# timer.net
KiCad netlist of a schematic drawn in EAGLE
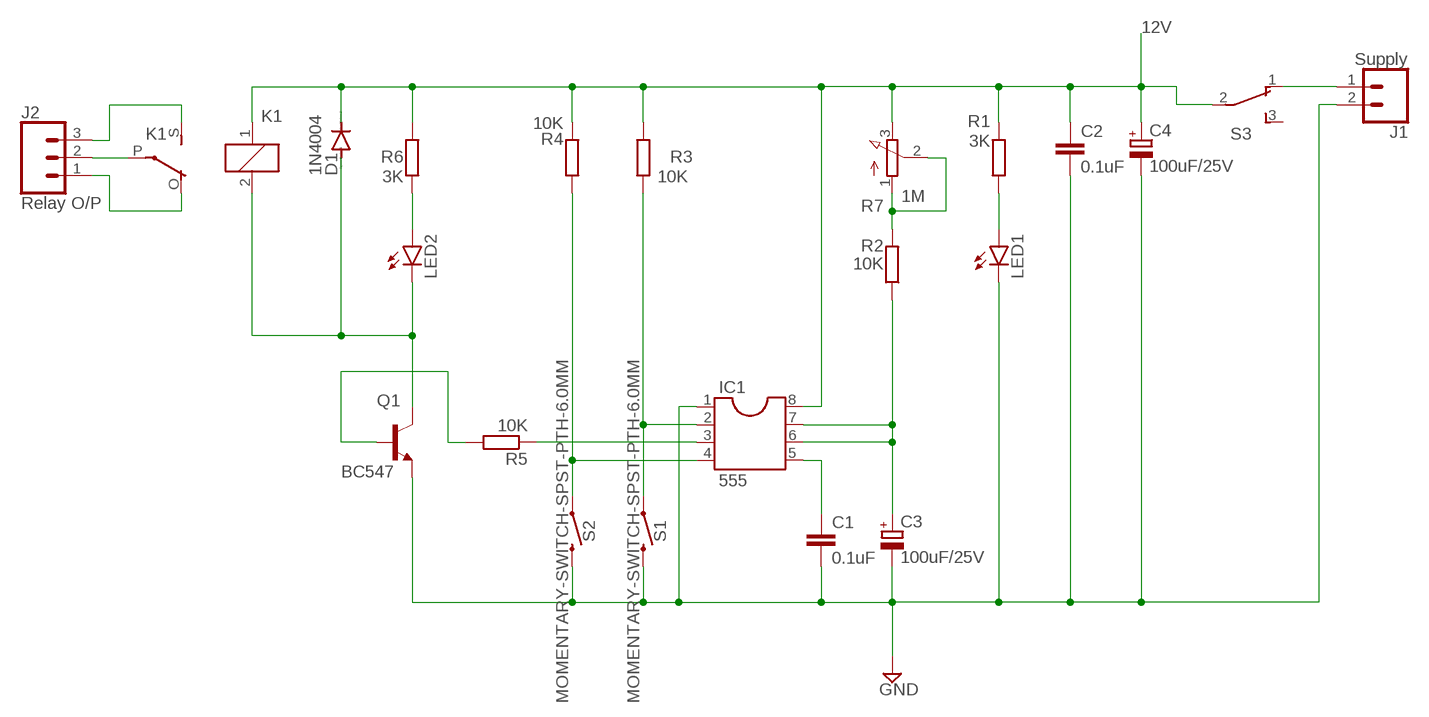
[diagram p0: schematic, sheet 1]

(export (version "E")
  (design (tool "Eeschema 10.0.6"))
  (components
    (comp (ref "C1")
      (value "0.1uF")
      (footprint "eagle-import:C025-050X050")
      (libsource (lib "eagle-import") (part "C-EU025-050X050"))
    )
    (comp (ref "C2")
      (value "0.1uF")
      (footprint "eagle-import:C025-050X050")
      (libsource (lib "eagle-import") (part "C-EU025-050X050"))
    )
    (comp (ref "C3")
      (value "100uF/25V")
      (footprint "eagle-import:E2,5-6")
      (libsource (lib "eagle-import") (part "CPOL-EUE2.5-6"))
    )
    (comp (ref "C4")
      (value "100uF/25V")
      (footprint "eagle-import:E2,5-6")
      (libsource (lib "eagle-import") (part "CPOL-EUE2.5-6"))
    )
    (comp (ref "D1")
      (value "1N4004")
      (footprint "eagle-import:DO41-10")
      (libsource (lib "eagle-import") (part "1N4004"))
    )
    (comp (ref "IC1")
      (value "555")
      (footprint "eagle-import:SOCKET-08")
      (libsource (lib "eagle-import") (part "DIL8S"))
    )
    (comp (ref "J1")
      (value "Supply")
      (footprint "eagle-import:SCREWTERMINAL-5MM-2")
      (libsource (lib "eagle-import") (part "CONN_025MM"))
    )
    (comp (ref "J2")
      (value "Relay O/P")
      (footprint "eagle-import:SCREWTERMINAL-5MM-3")
      (libsource (lib "eagle-import") (part "CONN_03-SCREW-5MM"))
    )
    (comp (ref "K1")
      (value "ZF112")
      (footprint "eagle-import:ZF112")
      (libsource (lib "eagle-import") (part "ZF112"))
    )
    (comp (ref "LED1")
      (value "LED5MM")
      (footprint "eagle-import:LED5MM")
      (libsource (lib "eagle-import") (part "LED5MM"))
    )
    (comp (ref "LED2")
      (value "LED5MM")
      (footprint "eagle-import:LED5MM")
      (libsource (lib "eagle-import") (part "LED5MM"))
    )
    (comp (ref "Q1")
      (value "BC547")
      (footprint "eagle-import:TO92")
      (libsource (lib "eagle-import") (part "BC547"))
    )
    (comp (ref "R1")
      (value "3K")
      (footprint "eagle-import:0207_10")
      (libsource (lib "eagle-import") (part "R-EU_0207/10"))
    )
    (comp (ref "R2")
      (value "10K")
      (footprint "eagle-import:0207_10")
      (libsource (lib "eagle-import") (part "R-EU_0207/10"))
    )
    (comp (ref "R3")
      (value "10K")
      (footprint "eagle-import:0207_10")
      (libsource (lib "eagle-import") (part "R-EU_0207/10"))
    )
    (comp (ref "R4")
      (value "10K")
      (footprint "eagle-import:0207_10")
      (libsource (lib "eagle-import") (part "R-EU_0207/10"))
    )
    (comp (ref "R5")
      (value "10K")
      (footprint "eagle-import:0207_10")
      (libsource (lib "eagle-import") (part "R-EU_0207/10"))
    )
    (comp (ref "R6")
      (value "3K")
      (footprint "eagle-import:0207_10")
      (libsource (lib "eagle-import") (part "R-EU_0207/10"))
    )
    (comp (ref "R7")
      (value "1M")
      (footprint "eagle-import:3RP_1610N")
      (libsource (lib "eagle-import") (part "3RP/1610N"))
    )
    (comp (ref "S1")
      (value "MOMENTARY-SWITCH-SPST-PTH-6.0MM")
      (footprint "eagle-import:TACTILE_SWITCH_PTH_6.0MM")
      (libsource (lib "eagle-import") (part "MOMENTARY-SWITCH-SPST-PTH-6.0MM"))
    )
    (comp (ref "S2")
      (value "MOMENTARY-SWITCH-SPST-PTH-6.0MM")
      (footprint "eagle-import:TACTILE_SWITCH_PTH_6.0MM")
      (libsource (lib "eagle-import") (part "MOMENTARY-SWITCH-SPST-PTH-6.0MM"))
    )
    (comp (ref "S3")
      (value "TL36YO")
      (footprint "eagle-import:TL3XYO")
      (libsource (lib "eagle-import") (part "TL36YO"))
    )
  )
  (nets
    (net (code "1") (name "/12V") (class "Default")
      (node (ref "C2") (pin "1") (pinfunction "1_1") (pintype "passive"))
      (node (ref "C4") (pin "+") (pinfunction "+_+") (pintype "passive"))
      (node (ref "D1") (pin "C") (pinfunction "C_C") (pintype "passive"))
      (node (ref "IC1") (pin "8") (pinfunction "8_8") (pintype "passive"))
      (node (ref "K1") (pin "1") (pinfunction "1_1") (pintype "passive"))
      (node (ref "R1") (pin "2") (pinfunction "2_2") (pintype "passive"))
      (node (ref "R3") (pin "2") (pinfunction "2_2") (pintype "passive"))
      (node (ref "R4") (pin "2") (pinfunction "2_2") (pintype "passive"))
      (node (ref "R6") (pin "2") (pinfunction "2_2") (pintype "passive"))
      (node (ref "R7") (pin "3") (pinfunction "E_3") (pintype "passive"))
      (node (ref "S3") (pin "2") (pinfunction "P_2") (pintype "passive"))
    )
    (net (code "2") (name "GND") (class "Default")
      (node (ref "C1") (pin "2") (pinfunction "2_2") (pintype "passive"))
      (node (ref "C2") (pin "2") (pinfunction "2_2") (pintype "passive"))
      (node (ref "C3") (pin "-") (pinfunction "-_-") (pintype "passive"))
      (node (ref "C4") (pin "-") (pinfunction "-_-") (pintype "passive"))
      (node (ref "IC1") (pin "1") (pinfunction "1_1") (pintype "passive"))
      (node (ref "J1") (pin "2") (pinfunction "2_2") (pintype "passive"))
      (node (ref "LED1") (pin "K") (pinfunction "C_K") (pintype "passive"))
      (node (ref "Q1") (pin "1") (pinfunction "E_1") (pintype "passive"))
      (node (ref "S1") (pin "3") (pinfunction "2_3") (pintype "passive"))
      (node (ref "S2") (pin "3") (pinfunction "2_3") (pintype "passive"))
    )
    (net (code "3") (name "Net-(C1-Pad1)") (class "Default")
      (node (ref "C1") (pin "1") (pinfunction "1_1") (pintype "passive"))
      (node (ref "IC1") (pin "5") (pinfunction "5_5") (pintype "passive"))
    )
    (net (code "4") (name "Net-(C3-Pad+)") (class "Default")
      (node (ref "C3") (pin "+") (pinfunction "+_+") (pintype "passive"))
      (node (ref "IC1") (pin "6") (pinfunction "6_6") (pintype "passive"))
      (node (ref "IC1") (pin "7") (pinfunction "7_7") (pintype "passive"))
      (node (ref "R2") (pin "1") (pinfunction "1_1") (pintype "passive"))
    )
    (net (code "5") (name "Net-(IC1-Pad2)") (class "Default")
      (node (ref "IC1") (pin "2") (pinfunction "2_2") (pintype "passive"))
      (node (ref "R3") (pin "1") (pinfunction "1_1") (pintype "passive"))
      (node (ref "S1") (pin "1") (pinfunction "1_1") (pintype "passive"))
    )
    (net (code "6") (name "Net-(IC1-Pad3)") (class "Default")
      (node (ref "IC1") (pin "3") (pinfunction "3_3") (pintype "passive"))
      (node (ref "R5") (pin "1") (pinfunction "1_1") (pintype "passive"))
    )
    (net (code "7") (name "Net-(IC1-Pad4)") (class "Default")
      (node (ref "IC1") (pin "4") (pinfunction "4_4") (pintype "passive"))
      (node (ref "R4") (pin "1") (pinfunction "1_1") (pintype "passive"))
      (node (ref "S2") (pin "1") (pinfunction "1_1") (pintype "passive"))
    )
    (net (code "8") (name "Net-(J2-Pad1)") (class "Default")
      (node (ref "J2") (pin "1") (pinfunction "1_1") (pintype "passive"))
      (node (ref "K1") (pin "O") (pinfunction "O_O") (pintype "passive"))
    )
    (net (code "9") (name "Net-(J2-Pad2)") (class "Default")
      (node (ref "J2") (pin "2") (pinfunction "2_2") (pintype "passive"))
      (node (ref "K1") (pin "P") (pinfunction "P_P") (pintype "passive"))
    )
    (net (code "10") (name "Net-(J2-Pad3)") (class "Default")
      (node (ref "J2") (pin "3") (pinfunction "3_3") (pintype "passive"))
      (node (ref "K1") (pin "S") (pinfunction "S_S") (pintype "passive"))
    )
    (net (code "11") (name "Net-(LED1-PadA)") (class "Default")
      (node (ref "LED1") (pin "A") (pinfunction "A_A") (pintype "passive"))
      (node (ref "R1") (pin "1") (pinfunction "1_1") (pintype "passive"))
    )
    (net (code "12") (name "Net-(LED2-C)") (class "Default")
      (node (ref "D1") (pin "A") (pinfunction "A_A") (pintype "passive"))
      (node (ref "K1") (pin "2") (pinfunction "2_2") (pintype "passive"))
      (node (ref "LED2") (pin "K") (pinfunction "C_K") (pintype "passive"))
      (node (ref "Q1") (pin "3") (pinfunction "C_3") (pintype "passive"))
    )
    (net (code "13") (name "Net-(LED2-PadA)") (class "Default")
      (node (ref "LED2") (pin "A") (pinfunction "A_A") (pintype "passive"))
      (node (ref "R6") (pin "1") (pinfunction "1_1") (pintype "passive"))
    )
    (net (code "14") (name "Net-(Q1-B)") (class "Default")
      (node (ref "Q1") (pin "2") (pinfunction "B_2") (pintype "passive"))
      (node (ref "R5") (pin "2") (pinfunction "2_2") (pintype "passive"))
    )
    (net (code "15") (name "Net-(R7-A)") (class "Default")
      (node (ref "R2") (pin "2") (pinfunction "2_2") (pintype "passive"))
      (node (ref "R7") (pin "1") (pinfunction "A_1") (pintype "passive"))
      (node (ref "R7") (pin "2") (pinfunction "S_2") (pintype "passive"))
    )
    (net (code "16") (name "Net-(S3-O)") (class "Default")
      (node (ref "J1") (pin "1") (pinfunction "1_1") (pintype "passive"))
      (node (ref "S3") (pin "1") (pinfunction "O_1") (pintype "passive"))
    )
    (net (code "17") (name "unconnected-(S3-S-Pad3)") (class "Default")
      (node (ref "S3") (pin "3") (pinfunction "S_3") (pintype "passive"))
    )
  )
)
